# scheme.net
KiCad netlist of a schematic drawn in EAGLE
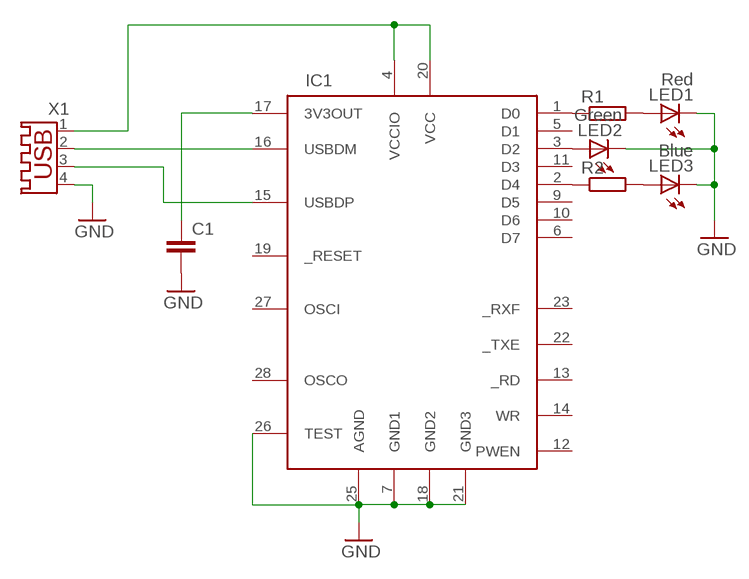
[diagram p0: schematic, sheet 1]

(export (version "E")
  (design (tool "Eeschema 10.0.6"))
  (components
    (comp (ref "C1")
      (value "C-EUC0805")
      (footprint "eagle-import:C0805")
      (libsource (lib "eagle-import") (part "C-EUC0805"))
    )
    (comp (ref "IC1")
      (value "FT245RL")
      (footprint "eagle-import:SSOP28DB")
      (libsource (lib "eagle-import") (part "FT245RL"))
    )
    (comp (ref "LED1")
      (value "Red")
      (footprint "eagle-import:LED5MM")
      (libsource (lib "eagle-import") (part "LED5MM"))
    )
    (comp (ref "LED2")
      (value "Green")
      (footprint "eagle-import:LED5MM")
      (libsource (lib "eagle-import") (part "LED5MM"))
    )
    (comp (ref "LED3")
      (value "Blue")
      (footprint "eagle-import:LED3MM")
      (libsource (lib "eagle-import") (part "LED3MM"))
    )
    (comp (ref "R1")
      (value "R-EU_0204/5")
      (footprint "eagle-import:0204_5")
      (libsource (lib "eagle-import") (part "R-EU_0204/5"))
    )
    (comp (ref "R2")
      (value "R-EU_0204/5")
      (footprint "eagle-import:0204_5")
      (libsource (lib "eagle-import") (part "R-EU_0204/5"))
    )
    (comp (ref "X1")
      (value "USB-A003")
      (footprint "eagle-import:USB-A003")
      (libsource (lib "eagle-import") (part "USB-A003"))
    )
  )
  (nets
    (net (code "1") (name "GND") (class "Default")
      (node (ref "C1") (pin "2") (pinfunction "2_2") (pintype "passive"))
      (node (ref "IC1") (pin "18") (pinfunction "GND2_18") (pintype "power_in"))
      (node (ref "IC1") (pin "21") (pinfunction "GND3_21") (pintype "power_in"))
      (node (ref "IC1") (pin "25") (pinfunction "AGND_25") (pintype "power_in"))
      (node (ref "IC1") (pin "26") (pinfunction "TEST_26") (pintype "input"))
      (node (ref "IC1") (pin "7") (pinfunction "GND1_7") (pintype "power_in"))
      (node (ref "LED1") (pin "K") (pinfunction "C_K") (pintype "passive"))
      (node (ref "LED2") (pin "K") (pinfunction "C_K") (pintype "passive"))
      (node (ref "LED3") (pin "K") (pinfunction "C_K") (pintype "passive"))
      (node (ref "X1") (pin "4") (pinfunction "4_4") (pintype "passive"))
    )
    (net (code "2") (name "Net-(IC1-3V3OUT)") (class "Default")
      (node (ref "C1") (pin "1") (pinfunction "1_1") (pintype "passive"))
      (node (ref "IC1") (pin "17") (pinfunction "3V3OUT_17") (pintype "output"))
    )
    (net (code "3") (name "Net-(IC1-D0)") (class "Default")
      (node (ref "IC1") (pin "1") (pinfunction "D0_1") (pintype "output"))
      (node (ref "R1") (pin "1") (pinfunction "1_1") (pintype "passive"))
    )
    (net (code "4") (name "Net-(IC1-D2)") (class "Default")
      (node (ref "IC1") (pin "3") (pinfunction "D2_3") (pintype "output"))
      (node (ref "LED2") (pin "A") (pinfunction "A_A") (pintype "passive"))
    )
    (net (code "5") (name "Net-(IC1-D4)") (class "Default")
      (node (ref "IC1") (pin "2") (pinfunction "D4_2") (pintype "output"))
      (node (ref "R2") (pin "1") (pinfunction "1_1") (pintype "passive"))
    )
    (net (code "6") (name "Net-(IC1-USBDM)") (class "Default")
      (node (ref "IC1") (pin "16") (pinfunction "USBDM_16") (pintype "bidirectional"))
      (node (ref "X1") (pin "2") (pinfunction "2_2") (pintype "passive"))
    )
    (net (code "7") (name "Net-(IC1-USBDP)") (class "Default")
      (node (ref "IC1") (pin "15") (pinfunction "USBDP_15") (pintype "bidirectional"))
      (node (ref "X1") (pin "3") (pinfunction "3_3") (pintype "passive"))
    )
    (net (code "8") (name "Net-(IC1-VCC)") (class "Default")
      (node (ref "IC1") (pin "20") (pinfunction "VCC_20") (pintype "power_in"))
      (node (ref "IC1") (pin "4") (pinfunction "VCCIO_4") (pintype "power_in"))
      (node (ref "X1") (pin "1") (pinfunction "1_1") (pintype "passive"))
    )
    (net (code "9") (name "Net-(LED1-PadA)") (class "Default")
      (node (ref "LED1") (pin "A") (pinfunction "A_A") (pintype "passive"))
      (node (ref "R1") (pin "2") (pinfunction "2_2") (pintype "passive"))
    )
    (net (code "10") (name "Net-(LED3-PadA)") (class "Default")
      (node (ref "LED3") (pin "A") (pinfunction "A_A") (pintype "passive"))
      (node (ref "R2") (pin "2") (pinfunction "2_2") (pintype "passive"))
    )
    (net (code "11") (name "unconnected-(IC1-D1-Pad5)") (class "Default")
      (node (ref "IC1") (pin "5") (pinfunction "D1_5") (pintype "input"))
    )
    (net (code "12") (name "unconnected-(IC1-D3-Pad11)") (class "Default")
      (node (ref "IC1") (pin "11") (pinfunction "D3_11") (pintype "input"))
    )
    (net (code "13") (name "unconnected-(IC1-D5-Pad9)") (class "Default")
      (node (ref "IC1") (pin "9") (pinfunction "D5_9") (pintype "input"))
    )
    (net (code "14") (name "unconnected-(IC1-D6-Pad10)") (class "Default")
      (node (ref "IC1") (pin "10") (pinfunction "D6_10") (pintype "input"))
    )
    (net (code "15") (name "unconnected-(IC1-D7-Pad6)") (class "Default")
      (node (ref "IC1") (pin "6") (pinfunction "D7_6") (pintype "input"))
    )
    (net (code "16") (name "unconnected-(IC1-OSCI-Pad27)") (class "Default")
      (node (ref "IC1") (pin "27") (pinfunction "OSCI_27") (pintype "input"))
    )
    (net (code "17") (name "unconnected-(IC1-OSCO-Pad28)") (class "Default")
      (node (ref "IC1") (pin "28") (pinfunction "OSCO_28") (pintype "output"))
    )
    (net (code "18") (name "unconnected-(IC1-PWEN-Pad12)") (class "Default")
      (node (ref "IC1") (pin "12") (pinfunction "PWEN_12") (pintype "bidirectional"))
    )
    (net (code "19") (name "unconnected-(IC1-WR-Pad14)") (class "Default")
      (node (ref "IC1") (pin "14") (pinfunction "WR_14") (pintype "bidirectional"))
    )
    (net (code "20") (name "unconnected-(IC1-_RD-Pad13)") (class "Default")
      (node (ref "IC1") (pin "13") (pinfunction "_RD_13") (pintype "bidirectional"))
    )
    (net (code "21") (name "unconnected-(IC1-_RESET-Pad19)") (class "Default")
      (node (ref "IC1") (pin "19") (pinfunction "_RESET_19") (pintype "input"))
    )
    (net (code "22") (name "unconnected-(IC1-_RXF-Pad23)") (class "Default")
      (node (ref "IC1") (pin "23") (pinfunction "_RXF_23") (pintype "bidirectional"))
    )
    (net (code "23") (name "unconnected-(IC1-_TXE-Pad22)") (class "Default")
      (node (ref "IC1") (pin "22") (pinfunction "_TXE_22") (pintype "bidirectional"))
    )
  )
)
